# Power.net
KiCad netlist of a schematic drawn in Altium Designer
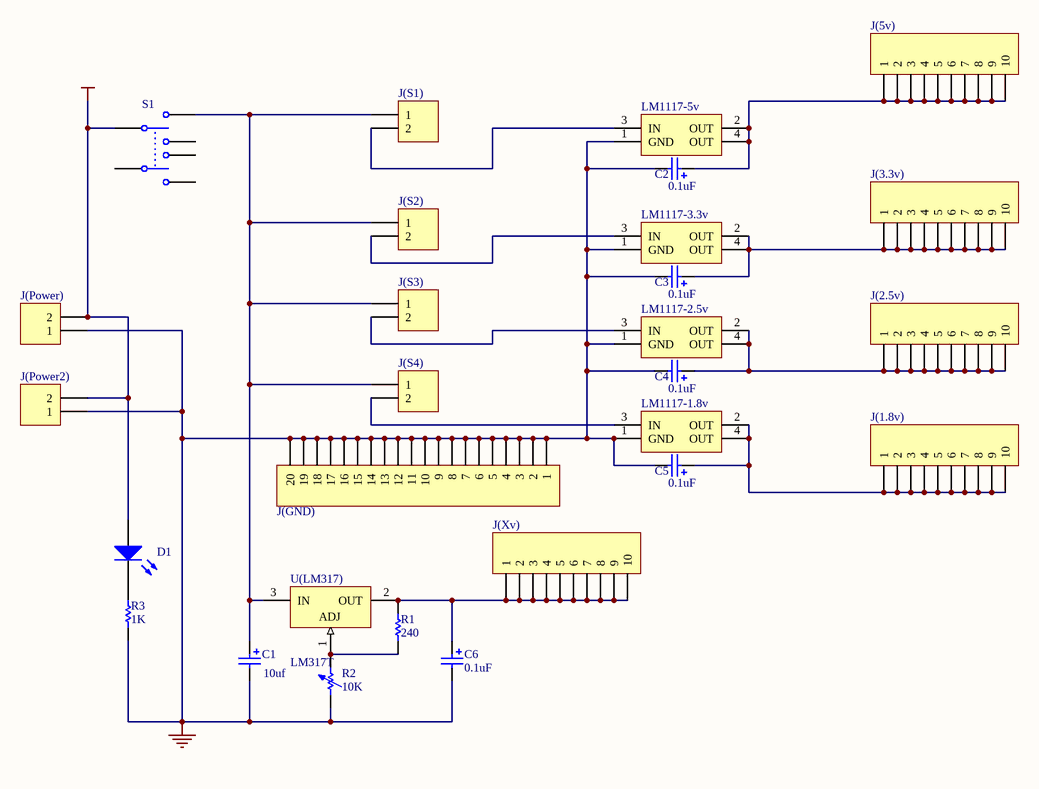
[diagram p0: Power.SchDoc]

(export (version "E")
  (design (tool "Eeschema 10.0.6"))
  (components
    (comp (ref "C1")
      (value "10uf")
      (footprint "CAPPR2-5X6.8")
      (description "Polarized Capacitor (Radial)")
      (fields (field (name "Comment") "Cap Pol1") (field (name "PUBLISHER") "Altium Limited"))
      (libsource (lib "Miscellaneous Devices") (part "Cap Pol1"))
    )
    (comp (ref "C2")
      (value "0.1uF")
      (footprint "CAPPR2-5X6.8")
      (description "Polarized Capacitor (Radial)")
      (fields (field (name "Comment") "Cap Pol1") (field (name "PUBLISHER") "Altium Limited"))
      (libsource (lib "Miscellaneous Devices") (part "Cap Pol1"))
    )
    (comp (ref "C3")
      (value "0.1uF")
      (footprint "CAPPR2-5X6.8")
      (description "Polarized Capacitor (Radial)")
      (fields (field (name "Comment") "Cap Pol1") (field (name "PUBLISHER") "Altium Limited"))
      (libsource (lib "Miscellaneous Devices") (part "Cap Pol1"))
    )
    (comp (ref "C4")
      (value "0.1uF")
      (footprint "CAPPR2-5X6.8")
      (description "Polarized Capacitor (Radial)")
      (fields (field (name "Comment") "Cap Pol1") (field (name "PUBLISHER") "Altium Limited"))
      (libsource (lib "Miscellaneous Devices") (part "Cap Pol1"))
    )
    (comp (ref "C5")
      (value "0.1uF")
      (footprint "CAPPR2-5X6.8")
      (description "Polarized Capacitor (Radial)")
      (fields (field (name "Comment") "Cap Pol1") (field (name "PUBLISHER") "Altium Limited"))
      (libsource (lib "Miscellaneous Devices") (part "Cap Pol1"))
    )
    (comp (ref "C6")
      (value "0.1uF")
      (footprint "CAPPR2-5X6.8")
      (description "Polarized Capacitor (Radial)")
      (fields (field (name "Comment") "Cap Pol1") (field (name "PUBLISHER") "Altium Limited"))
      (libsource (lib "Miscellaneous Devices") (part "Cap Pol1"))
    )
    (comp (ref "D1")
      (value "LED0")
      (footprint "HDR1X2")
      (description "Typical INFRARED GaAs LED")
      (fields (field (name "PUBLISHER") "Altium Limited"))
      (libsource (lib "Miscellaneous Devices") (part "LED0"))
    )
    (comp (ref "J(1.8v)")
      (value "Header 10")
      (footprint "HDR1X10")
      (description "Header, 10-Pin")
      (fields (field (name "PUBLISHER") "Altium Limited"))
      (libsource (lib "Miscellaneous Connectors") (part "Header 10"))
    )
    (comp (ref "J(2.5v)")
      (value "Header 10")
      (footprint "HDR1X10")
      (description "Header, 10-Pin")
      (fields (field (name "PUBLISHER") "Altium Limited"))
      (libsource (lib "Miscellaneous Connectors") (part "Header 10"))
    )
    (comp (ref "J(3.3v)")
      (value "Header 10")
      (footprint "HDR1X10")
      (description "Header, 10-Pin")
      (fields (field (name "PUBLISHER") "Altium Limited"))
      (libsource (lib "Miscellaneous Connectors") (part "Header 10"))
    )
    (comp (ref "J(5v)")
      (value "Header 10")
      (footprint "HDR1X10")
      (description "Header, 10-Pin")
      (fields (field (name "PUBLISHER") "Altium Limited"))
      (libsource (lib "Miscellaneous Connectors") (part "Header 10"))
    )
    (comp (ref "J(GND)")
      (value "Header 20")
      (footprint "HDR1X20")
      (description "Header, 20-Pin")
      (fields (field (name "PUBLISHER") "Altium Limited"))
      (libsource (lib "Miscellaneous Connectors") (part "Header 20"))
    )
    (comp (ref "J(Power)")
      (value "Header 2")
      (footprint "HDR1X2")
      (description "Header, 2-Pin")
      (fields (field (name "PUBLISHER") "Altium Limited"))
      (libsource (lib "Miscellaneous Connectors") (part "Header 2"))
    )
    (comp (ref "J(Power2)")
      (value "Header 2")
      (footprint "Power")
      (description "Header, 2-Pin")
      (fields (field (name "PUBLISHER") "Altium Limited"))
      (libsource (lib "Miscellaneous Connectors") (part "Header 2"))
    )
    (comp (ref "J(S1)")
      (value "Header 2")
      (footprint "HDR1X2")
      (description "Header, 2-Pin")
      (fields (field (name "PUBLISHER") "Altium Limited"))
      (libsource (lib "") (part "Header 2_1"))
    )
    (comp (ref "J(S2)")
      (value "Header 2")
      (footprint "HDR1X2")
      (description "Header, 2-Pin")
      (fields (field (name "PUBLISHER") "Altium Limited"))
      (libsource (lib "") (part "Header 2_1"))
    )
    (comp (ref "J(S3)")
      (value "Header 2")
      (footprint "HDR1X2")
      (description "Header, 2-Pin")
      (fields (field (name "PUBLISHER") "Altium Limited"))
      (libsource (lib "") (part "Header 2_1"))
    )
    (comp (ref "J(S4)")
      (value "Header 2")
      (footprint "HDR1X2")
      (description "Header, 2-Pin")
      (fields (field (name "PUBLISHER") "Altium Limited"))
      (libsource (lib "") (part "Header 2_1"))
    )
    (comp (ref "J(Xv)")
      (value "Header 10")
      (footprint "HDR1X10")
      (description "Header, 10-Pin")
      (fields (field (name "PUBLISHER") "Altium Limited"))
      (libsource (lib "Miscellaneous Connectors") (part "Header 10"))
    )
    (comp (ref "LM1117-1.8v")
      (value "REG1117-5")
      (footprint "ZZ311")
      (description "800mA and 1A Low Dropout Positive Regulator 2.85V, 3.3V, 5V, and Adjustable")
      (fields (field (name "PUBLISHER") "Altium Limited"))
      (libsource (lib "BB Power Mgt Voltage Regulator") (part "REG1117-5"))
    )
    (comp (ref "LM1117-2.5v")
      (value "REG1117-5")
      (footprint "ZZ311")
      (description "800mA and 1A Low Dropout Positive Regulator 2.85V, 3.3V, 5V, and Adjustable")
      (fields (field (name "PUBLISHER") "Altium Limited"))
      (libsource (lib "BB Power Mgt Voltage Regulator") (part "REG1117-5"))
    )
    (comp (ref "LM1117-3.3v")
      (value "REG1117-5")
      (footprint "ZZ311")
      (description "800mA and 1A Low Dropout Positive Regulator 2.85V, 3.3V, 5V, and Adjustable")
      (fields (field (name "PUBLISHER") "Altium Limited"))
      (libsource (lib "BB Power Mgt Voltage Regulator") (part "REG1117-5"))
    )
    (comp (ref "LM1117-5v")
      (value "REG1117-5")
      (footprint "ZZ311")
      (description "800mA and 1A Low Dropout Positive Regulator 2.85V, 3.3V, 5V, and Adjustable")
      (fields (field (name "PUBLISHER") "Altium Limited"))
      (libsource (lib "BB Power Mgt Voltage Regulator") (part "REG1117-5"))
    )
    (comp (ref "R1")
      (value "240")
      (footprint "AXIAL-0.3")
      (description "Resistor")
      (fields (field (name "Comment") "Res1") (field (name "PUBLISHER") "Altium Limited"))
      (libsource (lib "Miscellaneous Devices") (part "Res1"))
    )
    (comp (ref "R2")
      (value "10K")
      (footprint "PIN3")
      (description "Variable Resistor")
      (fields (field (name "Comment") "Res Adj1") (field (name "PUBLISHER") "Altium Limited"))
      (libsource (lib "Miscellaneous Devices") (part "Res Adj1"))
    )
    (comp (ref "R3")
      (value "1K")
      (footprint "AXIAL-0.3")
      (description "Resistor")
      (fields (field (name "Comment") "Res1") (field (name "PUBLISHER") "Altium Limited"))
      (libsource (lib "Miscellaneous Devices") (part "Res1"))
    )
    (comp (ref "S1")
      (value "SW-DPDT")
      (footprint "DPDT-6")
      (description "Double-Pole, Double-Throw Switch")
      (fields (field (name "PUBLISHER") "Altium Limited"))
      (libsource (lib "Miscellaneous Devices") (part "SW-DPDT"))
    )
    (comp (ref "U(LM317)")
      (value "LM317T")
      (footprint "TO-220")
      (description "Three-Terminal Adjustable Output Positive Voltage Regulator")
      (fields (field (name "PUBLISHER") "Altium Limited"))
      (libsource (lib "ON Semi Power Mgt Voltage Regulator") (part "LM317T"))
    )
  )
  (nets
    (net (code "1") (name "GND") (class "Default")
      (node (ref "C1") (pin "2") (pinfunction "2_2") (pintype "passive"))
      (node (ref "C2") (pin "2") (pinfunction "2_2") (pintype "passive"))
      (node (ref "C3") (pin "2") (pinfunction "2_2") (pintype "passive"))
      (node (ref "C4") (pin "2") (pinfunction "2_2") (pintype "passive"))
      (node (ref "C5") (pin "2") (pinfunction "2_2") (pintype "passive"))
      (node (ref "C6") (pin "2") (pinfunction "2_2") (pintype "passive"))
      (node (ref "J(GND)") (pin "1") (pinfunction "1_1") (pintype "passive"))
      (node (ref "J(GND)") (pin "10") (pinfunction "10_10") (pintype "passive"))
      (node (ref "J(GND)") (pin "11") (pinfunction "11_11") (pintype "passive"))
      (node (ref "J(GND)") (pin "12") (pinfunction "12_12") (pintype "passive"))
      (node (ref "J(GND)") (pin "13") (pinfunction "13_13") (pintype "passive"))
      (node (ref "J(GND)") (pin "14") (pinfunction "14_14") (pintype "passive"))
      (node (ref "J(GND)") (pin "15") (pinfunction "15_15") (pintype "passive"))
      (node (ref "J(GND)") (pin "16") (pinfunction "16_16") (pintype "passive"))
      (node (ref "J(GND)") (pin "17") (pinfunction "17_17") (pintype "passive"))
      (node (ref "J(GND)") (pin "18") (pinfunction "18_18") (pintype "passive"))
      (node (ref "J(GND)") (pin "19") (pinfunction "19_19") (pintype "passive"))
      (node (ref "J(GND)") (pin "2") (pinfunction "2_2") (pintype "passive"))
      (node (ref "J(GND)") (pin "20") (pinfunction "20_20") (pintype "passive"))
      (node (ref "J(GND)") (pin "3") (pinfunction "3_3") (pintype "passive"))
      (node (ref "J(GND)") (pin "4") (pinfunction "4_4") (pintype "passive"))
      (node (ref "J(GND)") (pin "5") (pinfunction "5_5") (pintype "passive"))
      (node (ref "J(GND)") (pin "6") (pinfunction "6_6") (pintype "passive"))
      (node (ref "J(GND)") (pin "7") (pinfunction "7_7") (pintype "passive"))
      (node (ref "J(GND)") (pin "8") (pinfunction "8_8") (pintype "passive"))
      (node (ref "J(GND)") (pin "9") (pinfunction "9_9") (pintype "passive"))
      (node (ref "J(Power)") (pin "1") (pinfunction "1_1") (pintype "passive"))
      (node (ref "J(Power2)") (pin "1") (pinfunction "1_1") (pintype "passive"))
      (node (ref "LM1117-1.8v") (pin "1") (pinfunction "GND_1") (pintype "power_in"))
      (node (ref "LM1117-2.5v") (pin "1") (pinfunction "GND_1") (pintype "power_in"))
      (node (ref "LM1117-3.3v") (pin "1") (pinfunction "GND_1") (pintype "power_in"))
      (node (ref "LM1117-5v") (pin "1") (pinfunction "GND_1") (pintype "power_in"))
      (node (ref "R2") (pin "1") (pinfunction "1_1") (pintype "passive"))
      (node (ref "R3") (pin "2") (pinfunction "2_2") (pintype "passive"))
    )
    (net (code "2") (name "Net-(C2-Pad1)") (class "Default")
      (node (ref "C2") (pin "1") (pinfunction "1_1") (pintype "passive"))
      (node (ref "J(5v)") (pin "1") (pinfunction "1_1") (pintype "passive"))
      (node (ref "J(5v)") (pin "10") (pinfunction "10_10") (pintype "passive"))
      (node (ref "J(5v)") (pin "2") (pinfunction "2_2") (pintype "passive"))
      (node (ref "J(5v)") (pin "3") (pinfunction "3_3") (pintype "passive"))
      (node (ref "J(5v)") (pin "4") (pinfunction "4_4") (pintype "passive"))
      (node (ref "J(5v)") (pin "5") (pinfunction "5_5") (pintype "passive"))
      (node (ref "J(5v)") (pin "6") (pinfunction "6_6") (pintype "passive"))
      (node (ref "J(5v)") (pin "7") (pinfunction "7_7") (pintype "passive"))
      (node (ref "J(5v)") (pin "8") (pinfunction "8_8") (pintype "passive"))
      (node (ref "J(5v)") (pin "9") (pinfunction "9_9") (pintype "passive"))
      (node (ref "LM1117-5v") (pin "2") (pinfunction "OUT_2") (pintype "power_in"))
      (node (ref "LM1117-5v") (pin "4") (pinfunction "OUT_4") (pintype "power_in"))
    )
    (net (code "3") (name "Net-(C3-Pad1)") (class "Default")
      (node (ref "C3") (pin "1") (pinfunction "1_1") (pintype "passive"))
      (node (ref "J(3.3v)") (pin "1") (pinfunction "1_1") (pintype "passive"))
      (node (ref "J(3.3v)") (pin "10") (pinfunction "10_10") (pintype "passive"))
      (node (ref "J(3.3v)") (pin "2") (pinfunction "2_2") (pintype "passive"))
      (node (ref "J(3.3v)") (pin "3") (pinfunction "3_3") (pintype "passive"))
      (node (ref "J(3.3v)") (pin "4") (pinfunction "4_4") (pintype "passive"))
      (node (ref "J(3.3v)") (pin "5") (pinfunction "5_5") (pintype "passive"))
      (node (ref "J(3.3v)") (pin "6") (pinfunction "6_6") (pintype "passive"))
      (node (ref "J(3.3v)") (pin "7") (pinfunction "7_7") (pintype "passive"))
      (node (ref "J(3.3v)") (pin "8") (pinfunction "8_8") (pintype "passive"))
      (node (ref "J(3.3v)") (pin "9") (pinfunction "9_9") (pintype "passive"))
      (node (ref "LM1117-3.3v") (pin "2") (pinfunction "OUT_2") (pintype "power_in"))
      (node (ref "LM1117-3.3v") (pin "4") (pinfunction "OUT_4") (pintype "power_in"))
    )
    (net (code "4") (name "Net-(C4-Pad1)") (class "Default")
      (node (ref "C4") (pin "1") (pinfunction "1_1") (pintype "passive"))
      (node (ref "J(2.5v)") (pin "1") (pinfunction "1_1") (pintype "passive"))
      (node (ref "J(2.5v)") (pin "10") (pinfunction "10_10") (pintype "passive"))
      (node (ref "J(2.5v)") (pin "2") (pinfunction "2_2") (pintype "passive"))
      (node (ref "J(2.5v)") (pin "3") (pinfunction "3_3") (pintype "passive"))
      (node (ref "J(2.5v)") (pin "4") (pinfunction "4_4") (pintype "passive"))
      (node (ref "J(2.5v)") (pin "5") (pinfunction "5_5") (pintype "passive"))
      (node (ref "J(2.5v)") (pin "6") (pinfunction "6_6") (pintype "passive"))
      (node (ref "J(2.5v)") (pin "7") (pinfunction "7_7") (pintype "passive"))
      (node (ref "J(2.5v)") (pin "8") (pinfunction "8_8") (pintype "passive"))
      (node (ref "J(2.5v)") (pin "9") (pinfunction "9_9") (pintype "passive"))
      (node (ref "LM1117-2.5v") (pin "2") (pinfunction "OUT_2") (pintype "power_in"))
      (node (ref "LM1117-2.5v") (pin "4") (pinfunction "OUT_4") (pintype "power_in"))
    )
    (net (code "5") (name "Net-(C5-Pad1)") (class "Default")
      (node (ref "C5") (pin "1") (pinfunction "1_1") (pintype "passive"))
      (node (ref "J(1.8v)") (pin "1") (pinfunction "1_1") (pintype "passive"))
      (node (ref "J(1.8v)") (pin "10") (pinfunction "10_10") (pintype "passive"))
      (node (ref "J(1.8v)") (pin "2") (pinfunction "2_2") (pintype "passive"))
      (node (ref "J(1.8v)") (pin "3") (pinfunction "3_3") (pintype "passive"))
      (node (ref "J(1.8v)") (pin "4") (pinfunction "4_4") (pintype "passive"))
      (node (ref "J(1.8v)") (pin "5") (pinfunction "5_5") (pintype "passive"))
      (node (ref "J(1.8v)") (pin "6") (pinfunction "6_6") (pintype "passive"))
      (node (ref "J(1.8v)") (pin "7") (pinfunction "7_7") (pintype "passive"))
      (node (ref "J(1.8v)") (pin "8") (pinfunction "8_8") (pintype "passive"))
      (node (ref "J(1.8v)") (pin "9") (pinfunction "9_9") (pintype "passive"))
      (node (ref "LM1117-1.8v") (pin "2") (pinfunction "OUT_2") (pintype "power_in"))
      (node (ref "LM1117-1.8v") (pin "4") (pinfunction "OUT_4") (pintype "power_in"))
    )
    (net (code "6") (name "Net-(D1-K)") (class "Default")
      (node (ref "D1") (pin "2") (pinfunction "K_2") (pintype "passive"))
      (node (ref "R3") (pin "1") (pinfunction "1_1") (pintype "passive"))
    )
    (net (code "7") (name "Net-(LM1117-1.8v-IN)") (class "Default")
      (node (ref "J(S4)") (pin "2") (pinfunction "2_2") (pintype "passive"))
      (node (ref "LM1117-1.8v") (pin "3") (pinfunction "IN_3") (pintype "power_in"))
    )
    (net (code "8") (name "Net-(LM1117-2.5v-IN)") (class "Default")
      (node (ref "J(S3)") (pin "2") (pinfunction "2_2") (pintype "passive"))
      (node (ref "LM1117-2.5v") (pin "3") (pinfunction "IN_3") (pintype "power_in"))
    )
    (net (code "9") (name "Net-(LM1117-3.3v-IN)") (class "Default")
      (node (ref "J(S2)") (pin "2") (pinfunction "2_2") (pintype "passive"))
      (node (ref "LM1117-3.3v") (pin "3") (pinfunction "IN_3") (pintype "power_in"))
    )
    (net (code "10") (name "Net-(LM1117-5v-IN)") (class "Default")
      (node (ref "J(S1)") (pin "2") (pinfunction "2_2") (pintype "passive"))
      (node (ref "LM1117-5v") (pin "3") (pinfunction "IN_3") (pintype "power_in"))
    )
    (net (code "11") (name "Net-(U(LM317)-ADJ)") (class "Default")
      (node (ref "R1") (pin "1") (pinfunction "1_1") (pintype "passive"))
      (node (ref "R2") (pin "2") (pinfunction "2_2") (pintype "passive"))
      (node (ref "U(LM317)") (pin "1") (pinfunction "ADJ_1") (pintype "input"))
    )
    (net (code "12") (name "Net-(U(LM317)-IN)") (class "Default")
      (node (ref "C1") (pin "1") (pinfunction "1_1") (pintype "passive"))
      (node (ref "J(S1)") (pin "1") (pinfunction "1_1") (pintype "passive"))
      (node (ref "J(S2)") (pin "1") (pinfunction "1_1") (pintype "passive"))
      (node (ref "J(S3)") (pin "1") (pinfunction "1_1") (pintype "passive"))
      (node (ref "J(S4)") (pin "1") (pinfunction "1_1") (pintype "passive"))
      (node (ref "S1") (pin "2") (pinfunction "2_2") (pintype "passive"))
      (node (ref "U(LM317)") (pin "3") (pinfunction "IN_3") (pintype "power_in"))
    )
    (net (code "13") (name "Net-(U(LM317)-OUT)") (class "Default")
      (node (ref "C6") (pin "1") (pinfunction "1_1") (pintype "passive"))
      (node (ref "J(Xv)") (pin "1") (pinfunction "1_1") (pintype "passive"))
      (node (ref "J(Xv)") (pin "10") (pinfunction "10_10") (pintype "passive"))
      (node (ref "J(Xv)") (pin "2") (pinfunction "2_2") (pintype "passive"))
      (node (ref "J(Xv)") (pin "3") (pinfunction "3_3") (pintype "passive"))
      (node (ref "J(Xv)") (pin "4") (pinfunction "4_4") (pintype "passive"))
      (node (ref "J(Xv)") (pin "5") (pinfunction "5_5") (pintype "passive"))
      (node (ref "J(Xv)") (pin "6") (pinfunction "6_6") (pintype "passive"))
      (node (ref "J(Xv)") (pin "7") (pinfunction "7_7") (pintype "passive"))
      (node (ref "J(Xv)") (pin "8") (pinfunction "8_8") (pintype "passive"))
      (node (ref "J(Xv)") (pin "9") (pinfunction "9_9") (pintype "passive"))
      (node (ref "R1") (pin "2") (pinfunction "2_2") (pintype "passive"))
      (node (ref "U(LM317)") (pin "2") (pinfunction "OUT_2") (pintype "power_in"))
    )
    (net (code "14") (name "VCC") (class "Default")
      (node (ref "D1") (pin "1") (pinfunction "A_1") (pintype "passive"))
      (node (ref "J(Power)") (pin "2") (pinfunction "2_2") (pintype "passive"))
      (node (ref "J(Power2)") (pin "2") (pinfunction "2_2") (pintype "passive"))
      (node (ref "S1") (pin "1") (pinfunction "1_1") (pintype "passive"))
    )
    (net (code "15") (name "unconnected-(S1-Pad3)") (class "Default")
      (node (ref "S1") (pin "3") (pinfunction "3_3") (pintype "passive"))
    )
    (net (code "16") (name "unconnected-(S1-Pad4)") (class "Default")
      (node (ref "S1") (pin "4") (pinfunction "4_4") (pintype "passive"))
    )
    (net (code "17") (name "unconnected-(S1-Pad5)") (class "Default")
      (node (ref "S1") (pin "5") (pinfunction "5_5") (pintype "passive"))
    )
    (net (code "18") (name "unconnected-(S1-Pad6)") (class "Default")
      (node (ref "S1") (pin "6") (pinfunction "6_6") (pintype "passive"))
    )
  )
)
